# Relay_Old.net
KiCad netlist of a schematic drawn in Altium Designer
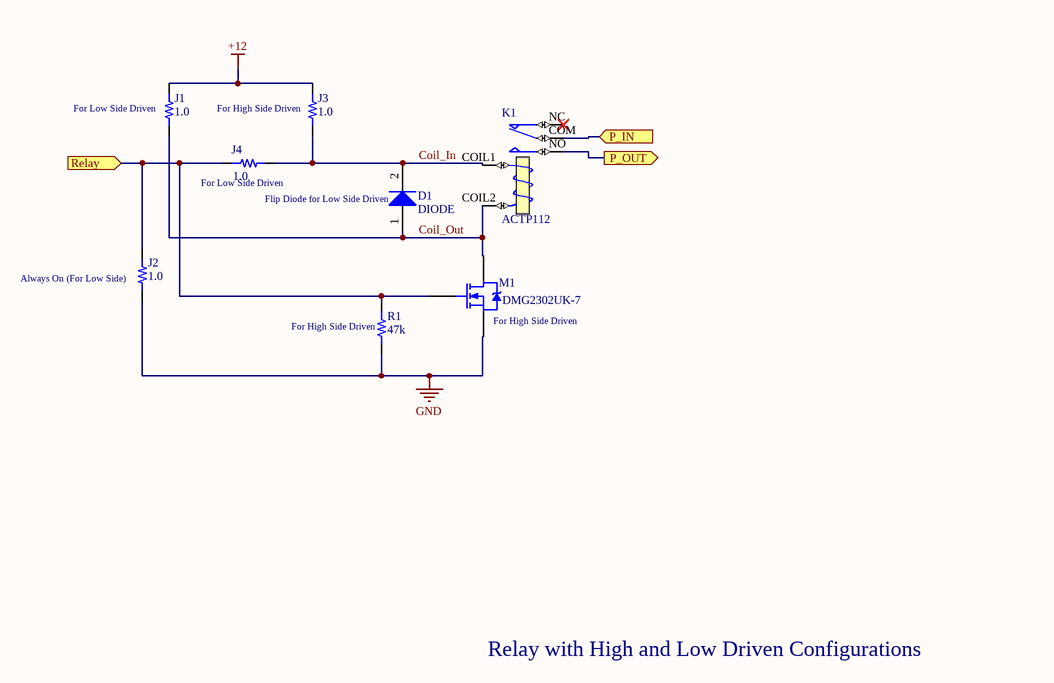
[diagram p0: Relay Old.SchDoc]

(export (version "E")
  (design (tool "Eeschema 10.0.6"))
  (components
    (comp (ref "D1")
      (value "DIODE")
      (footprint "SOD123F")
      (description "Diode Super Barrier 40V 1A Surface Mount SOD-123F")
      (fields (field (name "POWER") "40V") (field (name "MFRPARTNO") "1N5819HW1-7-F"))
      (libsource (lib "Altium-Lib") (part "DIODE"))
    )
    (comp (ref "J1")
      (value "1.0")
      (footprint "RES 0805/2012")
      (fields
        (field (name "TOLERANCE") "10%")
        (field (name "POWER") "1/10W")
        (field (name "Comment") "Resistor 1.0 0805 1/10W 10%")
        (field (name "CREATED_BY") "Nick Mah")
      )
      (libsource (lib "Altium-Lib") (part "Resistor"))
    )
    (comp (ref "J2")
      (value "1.0")
      (footprint "RES 0805/2012")
      (fields
        (field (name "TOLERANCE") "10%")
        (field (name "POWER") "1/10W")
        (field (name "Comment") "Resistor 1.0 0805 1/10W 10%")
        (field (name "CREATED_BY") "Nick Mah")
      )
      (libsource (lib "Altium-Lib") (part "Resistor"))
    )
    (comp (ref "J3")
      (value "1.0")
      (footprint "RES 0805/2012")
      (fields
        (field (name "TOLERANCE") "10%")
        (field (name "POWER") "1/10W")
        (field (name "Comment") "Resistor 1.0 0805 1/10W 10%")
        (field (name "CREATED_BY") "Nick Mah")
      )
      (libsource (lib "Altium-Lib") (part "Resistor"))
    )
    (comp (ref "J4")
      (value "1.0")
      (footprint "RES 0805/2012")
      (fields
        (field (name "TOLERANCE") "10%")
        (field (name "POWER") "1/10W")
        (field (name "Comment") "Resistor 1.0 0805 1/10W 10%")
        (field (name "CREATED_BY") "Nick Mah")
      )
      (libsource (lib "Altium-Lib") (part "Resistor"))
    )
    (comp (ref "K1")
      (value "ACTP112")
      (footprint "ACTP112")
      (fields (field (name "PUBLISHER") "Altium Limited"))
      (libsource (lib "Altium-Lib") (part "ACTP112"))
    )
    (comp (ref "M1")
      (value "DMG2302UK-7")
      (footprint "SOT23-3")
      (description "MOSFET N-CHANNEL 30V 5A SOT23")
      (fields (field (name "CREATED_BY") "Angel"))
      (libsource (lib "Altium-Lib") (part "DMG2302UK-7"))
    )
    (comp (ref "R1")
      (value "47k")
      (footprint "RES 0805/2012")
      (fields
        (field (name "TOLERANCE") "10%")
        (field (name "POWER") "1/10W")
        (field (name "Comment") "Resistor 47k 0805 1/10W 10%")
        (field (name "CREATED_BY") "Nick Mah")
      )
      (libsource (lib "Altium-Lib") (part "Resistor"))
    )
  )
  (nets
    (net (code "1") (name "+12") (class "Default")
      (node (ref "J1") (pin "1") (pinfunction "1_1") (pintype "passive"))
      (node (ref "J3") (pin "1") (pinfunction "1_1") (pintype "passive"))
    )
    (net (code "2") (name "/Coil_In") (class "Default")
      (node (ref "D1") (pin "2") (pinfunction "K_2") (pintype "passive"))
      (node (ref "J3") (pin "2") (pinfunction "2_2") (pintype "passive"))
      (node (ref "J4") (pin "2") (pinfunction "2_2") (pintype "passive"))
      (node (ref "K1") (pin "COIL1") (pinfunction "T1_COIL1") (pintype "bidirectional"))
    )
    (net (code "3") (name "/Coil_Out") (class "Default")
      (node (ref "D1") (pin "1") (pinfunction "A_1") (pintype "passive"))
      (node (ref "J1") (pin "2") (pinfunction "2_2") (pintype "passive"))
      (node (ref "K1") (pin "COIL2") (pinfunction "T2_COIL2") (pintype "bidirectional"))
      (node (ref "M1") (pin "3") (pinfunction "D_3") (pintype "passive"))
    )
    (net (code "4") (name "/P_IN") (class "Default")
      (node (ref "K1") (pin "COM") (pinfunction "COM_COM") (pintype "bidirectional"))
    )
    (net (code "5") (name "/P_OUT") (class "Default")
      (node (ref "K1") (pin "NO") (pinfunction "NO_NO") (pintype "bidirectional"))
    )
    (net (code "6") (name "/Relay") (class "Default")
      (node (ref "J2") (pin "1") (pinfunction "1_1") (pintype "passive"))
      (node (ref "J4") (pin "1") (pinfunction "1_1") (pintype "passive"))
      (node (ref "M1") (pin "1") (pinfunction "G_1") (pintype "passive"))
      (node (ref "R1") (pin "2") (pinfunction "2_2") (pintype "passive"))
    )
    (net (code "7") (name "GND") (class "Default")
      (node (ref "J2") (pin "2") (pinfunction "2_2") (pintype "passive"))
      (node (ref "M1") (pin "2") (pinfunction "S_2") (pintype "passive"))
      (node (ref "R1") (pin "1") (pinfunction "1_1") (pintype "passive"))
    )
    (net (code "8") (name "unconnected-(K1-PadNC)") (class "Default")
      (node (ref "K1") (pin "NC") (pinfunction "NC_NC") (pintype "bidirectional+no_connect"))
    )
  )
)
